# ASIC_Interposer.net
KiCad netlist of a schematic drawn in Altium Designer
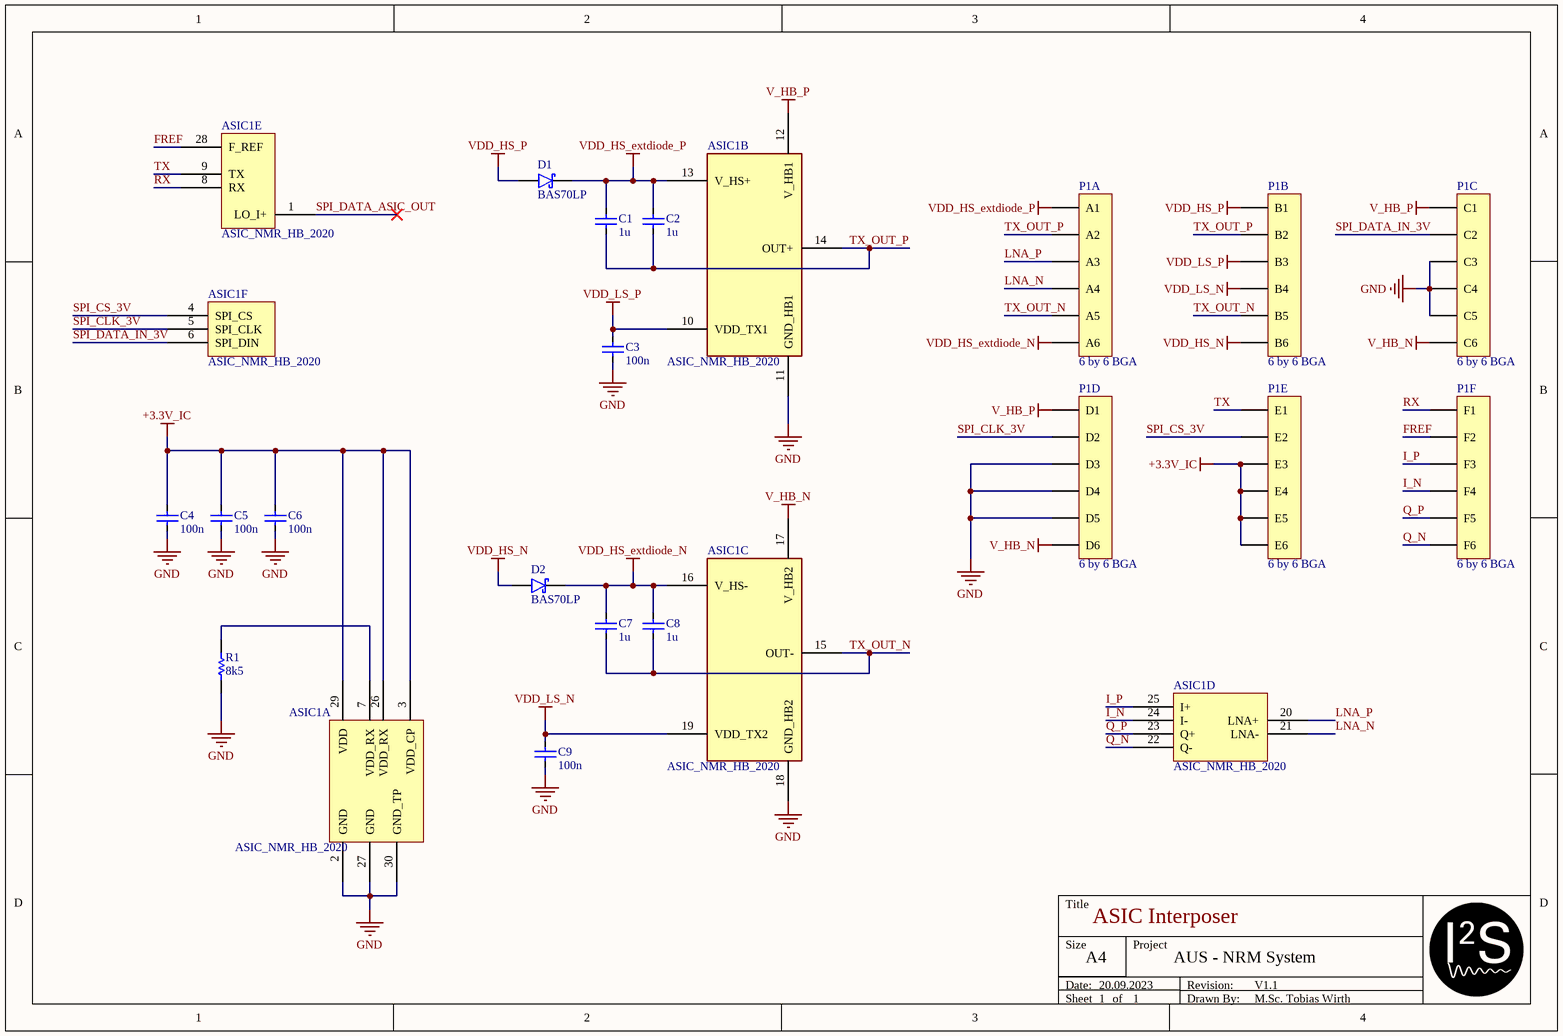
[diagram p0: ASIC_Interposer.SchDoc]

(export (version "E")
  (design (tool "Eeschema 10.0.6"))
  (components
    (comp (ref "ASIC1")
      (value "ASIC_NMR_HB_2020")
      (footprint "ASIC_NMR_HB_2020")
      (libsource (lib "IIS-Lib_TW") (part "ASIC_NMR_HB_2020"))
    )
    (comp (ref "C1")
      (value "1u")
      (footprint "CAP_0402")
      (description "1µ @ 16V max.")
      (libsource (lib "IIS-Lib_TW") (part "Cap"))
    )
    (comp (ref "C2")
      (value "1u")
      (footprint "CAP_0402")
      (description "1µ @ 16V max.")
      (libsource (lib "IIS-Lib_TW") (part "Cap"))
    )
    (comp (ref "C3") (value "100n") (footprint "CAP_0402") (libsource (lib "IIS-Lib_TW") (part "Cap")))
    (comp (ref "C4") (value "100n") (footprint "CAP_0402") (libsource (lib "IIS-Lib_TW") (part "Cap")))
    (comp (ref "C5") (value "100n") (footprint "CAP_0402") (libsource (lib "IIS-Lib_TW") (part "Cap")))
    (comp (ref "C6") (value "100n") (footprint "CAP_0402") (libsource (lib "IIS-Lib_TW") (part "Cap")))
    (comp (ref "C7")
      (value "1u")
      (footprint "CAP_0402")
      (description "1µ @ 16V max.")
      (libsource (lib "IIS-Lib_TW") (part "Cap"))
    )
    (comp (ref "C8")
      (value "1u")
      (footprint "CAP_0402")
      (description "1µ @ 16V max.")
      (libsource (lib "IIS-Lib_TW") (part "Cap"))
    )
    (comp (ref "C9") (value "100n") (footprint "CAP_0402") (libsource (lib "IIS-Lib_TW") (part "Cap")))
    (comp (ref "D1")
      (value "BAS70LP")
      (footprint "DFN65P101X53-2L")
      (libsource (lib "IIS-Lib_TW") (part "Schottky Diode"))
    )
    (comp (ref "D2")
      (value "BAS70LP")
      (footprint "DFN65P101X53-2L")
      (libsource (lib "IIS-Lib_TW") (part "Schottky Diode"))
    )
    (comp (ref "P1")
      (value "6 by 6 BGA")
      (footprint "BGA36C230P6X6_1500X1500X190 - ASIC")
      (libsource (lib "IIS-Lib_TW") (part "BGA_6x6"))
    )
    (comp (ref "R1") (value "8k5") (footprint "RES_0402") (libsource (lib "IIS-Lib_TW") (part "Res")))
  )
  (nets
    (net (code "1") (name "+3.3V_IC") (class "Default")
      (node (ref "ASIC1") (pin "26") (pinfunction "VDD_RX_26") (pintype "passive"))
      (node (ref "ASIC1") (pin "29") (pinfunction "VDD_29") (pintype "passive"))
      (node (ref "ASIC1") (pin "3") (pinfunction "VDD_CP_3") (pintype "passive"))
      (node (ref "C4") (pin "1") (pinfunction "1_1") (pintype "passive"))
      (node (ref "C5") (pin "1") (pinfunction "1_1") (pintype "passive"))
      (node (ref "C6") (pin "1") (pinfunction "1_1") (pintype "passive"))
      (node (ref "P1") (pin "E3") (pinfunction "E3_E3") (pintype "passive"))
      (node (ref "P1") (pin "E4") (pinfunction "E4_E4") (pintype "passive"))
      (node (ref "P1") (pin "E5") (pinfunction "E5_E5") (pintype "passive"))
      (node (ref "P1") (pin "E6") (pinfunction "E6_E6") (pintype "passive"))
    )
    (net (code "2") (name "/FREF") (class "Default")
      (node (ref "ASIC1") (pin "28") (pinfunction "F_REF_28") (pintype "passive"))
      (node (ref "P1") (pin "F2") (pinfunction "F2_F2") (pintype "passive"))
    )
    (net (code "3") (name "/I_N") (class "Default")
      (node (ref "ASIC1") (pin "24") (pinfunction "I-_24") (pintype "passive"))
      (node (ref "P1") (pin "F4") (pinfunction "F4_F4") (pintype "passive"))
    )
    (net (code "4") (name "/I_P") (class "Default")
      (node (ref "ASIC1") (pin "25") (pinfunction "I+_25") (pintype "passive"))
      (node (ref "P1") (pin "F3") (pinfunction "F3_F3") (pintype "passive"))
    )
    (net (code "5") (name "/LNA_N") (class "Default")
      (node (ref "ASIC1") (pin "21") (pinfunction "LNA-_21") (pintype "passive"))
      (node (ref "P1") (pin "A4") (pinfunction "A4_A4") (pintype "passive"))
    )
    (net (code "6") (name "/LNA_P") (class "Default")
      (node (ref "ASIC1") (pin "20") (pinfunction "LNA+_20") (pintype "passive"))
      (node (ref "P1") (pin "A3") (pinfunction "A3_A3") (pintype "passive"))
    )
    (net (code "7") (name "/Q_N") (class "Default")
      (node (ref "ASIC1") (pin "22") (pinfunction "Q-_22") (pintype "passive"))
      (node (ref "P1") (pin "F6") (pinfunction "F6_F6") (pintype "passive"))
    )
    (net (code "8") (name "/Q_P") (class "Default")
      (node (ref "ASIC1") (pin "23") (pinfunction "Q+_23") (pintype "passive"))
      (node (ref "P1") (pin "F5") (pinfunction "F5_F5") (pintype "passive"))
    )
    (net (code "9") (name "/RX") (class "Default")
      (node (ref "ASIC1") (pin "8") (pinfunction "RX_8") (pintype "passive"))
      (node (ref "P1") (pin "F1") (pinfunction "F1_F1") (pintype "passive"))
    )
    (net (code "10") (name "/SPI_CLK_3V") (class "Default")
      (node (ref "ASIC1") (pin "5") (pinfunction "SPI_CLK_5") (pintype "passive"))
      (node (ref "P1") (pin "D2") (pinfunction "D2_D2") (pintype "passive"))
    )
    (net (code "11") (name "/SPI_CS_3V") (class "Default")
      (node (ref "ASIC1") (pin "4") (pinfunction "SPI_CS_4") (pintype "passive"))
      (node (ref "P1") (pin "E2") (pinfunction "E2_E2") (pintype "passive"))
    )
    (net (code "12") (name "/SPI_DATA_ASIC_OUT") (class "Default")
      (node (ref "ASIC1") (pin "1") (pinfunction "LO_I+_1") (pintype "passive+no_connect"))
    )
    (net (code "13") (name "/SPI_DATA_IN_3V") (class "Default")
      (node (ref "ASIC1") (pin "6") (pinfunction "SPI_DIN_6") (pintype "passive"))
      (node (ref "P1") (pin "C2") (pinfunction "C2_C2") (pintype "passive"))
    )
    (net (code "14") (name "/TX") (class "Default")
      (node (ref "ASIC1") (pin "9") (pinfunction "TX_9") (pintype "passive"))
      (node (ref "P1") (pin "E1") (pinfunction "E1_E1") (pintype "passive"))
    )
    (net (code "15") (name "/TX_OUT_N") (class "Default")
      (node (ref "ASIC1") (pin "15") (pinfunction "OUT-_15") (pintype "passive"))
      (node (ref "C7") (pin "2") (pinfunction "2_2") (pintype "passive"))
      (node (ref "C8") (pin "2") (pinfunction "2_2") (pintype "passive"))
      (node (ref "P1") (pin "A5") (pinfunction "A5_A5") (pintype "passive"))
      (node (ref "P1") (pin "B5") (pinfunction "B5_B5") (pintype "passive"))
    )
    (net (code "16") (name "/TX_OUT_P") (class "Default")
      (node (ref "ASIC1") (pin "14") (pinfunction "OUT+_14") (pintype "passive"))
      (node (ref "C1") (pin "2") (pinfunction "2_2") (pintype "passive"))
      (node (ref "C2") (pin "2") (pinfunction "2_2") (pintype "passive"))
      (node (ref "P1") (pin "A2") (pinfunction "A2_A2") (pintype "passive"))
      (node (ref "P1") (pin "B2") (pinfunction "B2_B2") (pintype "passive"))
    )
    (net (code "17") (name "GND") (class "Default")
      (node (ref "ASIC1") (pin "11") (pinfunction "GND_HB1_11") (pintype "passive"))
      (node (ref "ASIC1") (pin "18") (pinfunction "GND_HB2_18") (pintype "passive"))
      (node (ref "ASIC1") (pin "2") (pinfunction "GND_2") (pintype "passive"))
      (node (ref "ASIC1") (pin "27") (pinfunction "GND_27") (pintype "passive"))
      (node (ref "ASIC1") (pin "30") (pinfunction "GND_TP_30") (pintype "passive"))
      (node (ref "C3") (pin "2") (pinfunction "2_2") (pintype "passive"))
      (node (ref "C4") (pin "2") (pinfunction "2_2") (pintype "passive"))
      (node (ref "C5") (pin "2") (pinfunction "2_2") (pintype "passive"))
      (node (ref "C6") (pin "2") (pinfunction "2_2") (pintype "passive"))
      (node (ref "C9") (pin "2") (pinfunction "2_2") (pintype "passive"))
      (node (ref "P1") (pin "C3") (pinfunction "C3_C3") (pintype "passive"))
      (node (ref "P1") (pin "C4") (pinfunction "C4_C4") (pintype "passive"))
      (node (ref "P1") (pin "C5") (pinfunction "C5_C5") (pintype "passive"))
      (node (ref "P1") (pin "D3") (pinfunction "D3_D3") (pintype "passive"))
      (node (ref "P1") (pin "D4") (pinfunction "D4_D4") (pintype "passive"))
      (node (ref "P1") (pin "D5") (pinfunction "D5_D5") (pintype "passive"))
      (node (ref "R1") (pin "1") (pinfunction "1_1") (pintype "passive"))
    )
    (net (code "18") (name "Net-(ASIC1A-VDD_RX-Pad7)") (class "Default")
      (node (ref "ASIC1") (pin "7") (pinfunction "VDD_RX_7") (pintype "passive"))
      (node (ref "R1") (pin "2") (pinfunction "2_2") (pintype "passive"))
    )
    (net (code "19") (name "VDD_HS_N") (class "Default")
      (node (ref "D2") (pin "1") (pinfunction "1_1") (pintype "passive"))
      (node (ref "P1") (pin "B6") (pinfunction "B6_B6") (pintype "passive"))
    )
    (net (code "20") (name "VDD_HS_P") (class "Default")
      (node (ref "D1") (pin "1") (pinfunction "1_1") (pintype "passive"))
      (node (ref "P1") (pin "B1") (pinfunction "B1_B1") (pintype "passive"))
    )
    (net (code "21") (name "VDD_HS_extdiode_N") (class "Default")
      (node (ref "ASIC1") (pin "16") (pinfunction "V_HS-_16") (pintype "passive"))
      (node (ref "C7") (pin "1") (pinfunction "1_1") (pintype "passive"))
      (node (ref "C8") (pin "1") (pinfunction "1_1") (pintype "passive"))
      (node (ref "D2") (pin "2") (pinfunction "2_2") (pintype "passive"))
      (node (ref "P1") (pin "A6") (pinfunction "A6_A6") (pintype "passive"))
    )
    (net (code "22") (name "VDD_HS_extdiode_P") (class "Default")
      (node (ref "ASIC1") (pin "13") (pinfunction "V_HS+_13") (pintype "passive"))
      (node (ref "C1") (pin "1") (pinfunction "1_1") (pintype "passive"))
      (node (ref "C2") (pin "1") (pinfunction "1_1") (pintype "passive"))
      (node (ref "D1") (pin "2") (pinfunction "2_2") (pintype "passive"))
      (node (ref "P1") (pin "A1") (pinfunction "A1_A1") (pintype "passive"))
    )
    (net (code "23") (name "VDD_LS_N") (class "Default")
      (node (ref "ASIC1") (pin "19") (pinfunction "VDD_TX2_19") (pintype "passive"))
      (node (ref "C9") (pin "1") (pinfunction "1_1") (pintype "passive"))
      (node (ref "P1") (pin "B4") (pinfunction "B4_B4") (pintype "passive"))
    )
    (net (code "24") (name "VDD_LS_P") (class "Default")
      (node (ref "ASIC1") (pin "10") (pinfunction "VDD_TX1_10") (pintype "passive"))
      (node (ref "C3") (pin "1") (pinfunction "1_1") (pintype "passive"))
      (node (ref "P1") (pin "B3") (pinfunction "B3_B3") (pintype "passive"))
    )
    (net (code "25") (name "V_HB_N") (class "Default")
      (node (ref "ASIC1") (pin "17") (pinfunction "V_HB2_17") (pintype "passive"))
      (node (ref "P1") (pin "C6") (pinfunction "C6_C6") (pintype "passive"))
      (node (ref "P1") (pin "D6") (pinfunction "D6_D6") (pintype "passive"))
    )
    (net (code "26") (name "V_HB_P") (class "Default")
      (node (ref "ASIC1") (pin "12") (pinfunction "V_HB1_12") (pintype "passive"))
      (node (ref "P1") (pin "C1") (pinfunction "C1_C1") (pintype "passive"))
      (node (ref "P1") (pin "D1") (pinfunction "D1_D1") (pintype "passive"))
    )
  )
)
